# FlightComputer.net
KiCad netlist of a schematic drawn in EAGLE
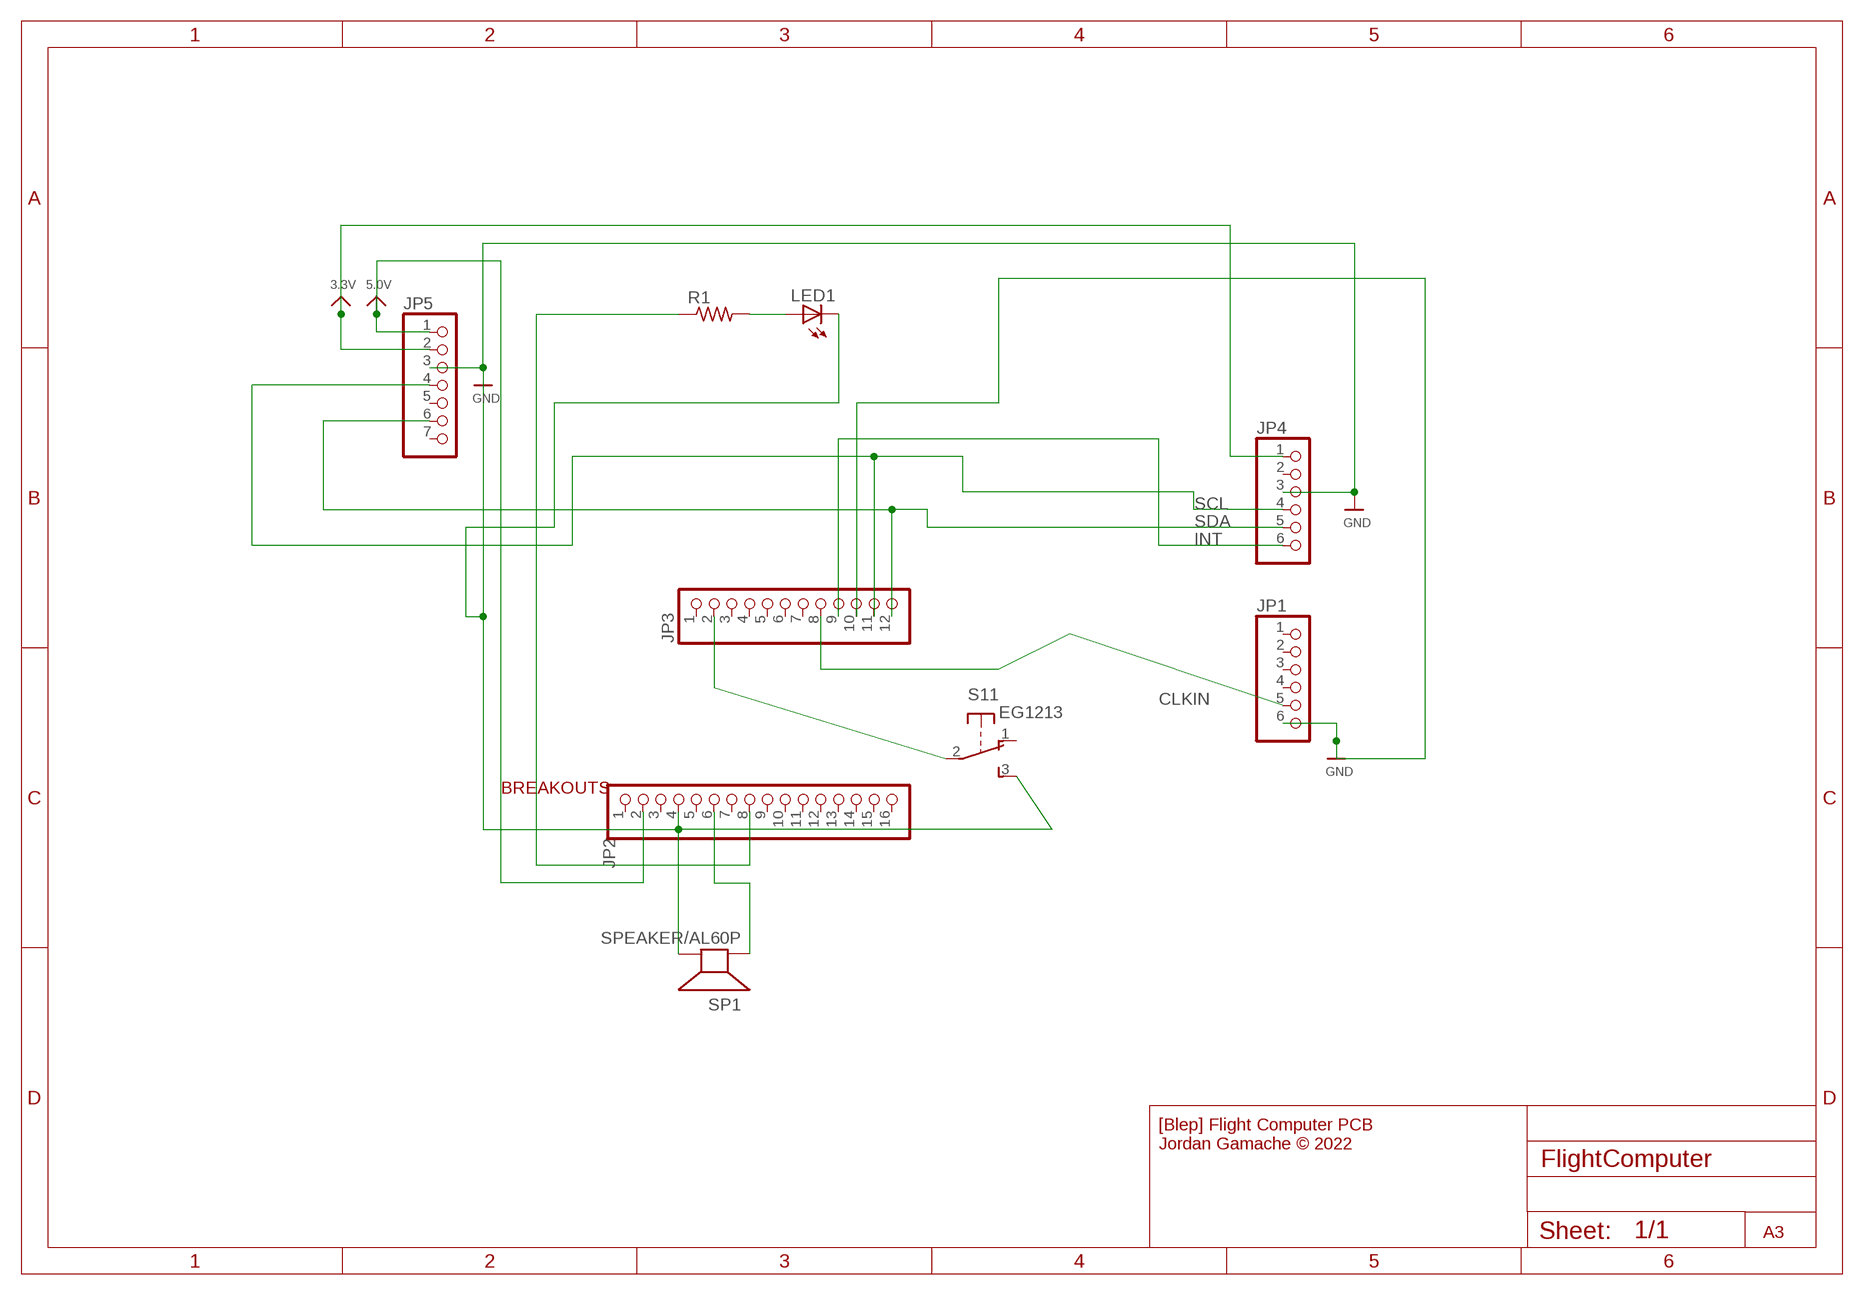
[diagram p0: schematic, sheet 1]

(export (version "E")
  (design (tool "Eeschema 10.0.6"))
  (components
    (comp (ref "JP1")
      (value "HEADER-1X6ROUND")
      (footprint "eagle-import:1X06_ROUND")
      (libsource (lib "eagle-import") (part "HEADER-1X6ROUND"))
    )
    (comp (ref "JP2")
      (value "HEADER-1X16ROUND")
      (footprint "eagle-import:1X16_ROUND")
      (libsource (lib "eagle-import") (part "HEADER-1X16ROUND"))
    )
    (comp (ref "JP3")
      (value "HEADER-1X12")
      (footprint "eagle-import:1X12_ROUND")
      (libsource (lib "eagle-import") (part "HEADER-1X12"))
    )
    (comp (ref "JP4")
      (value "HEADER-1X670MIL")
      (footprint "eagle-import:1X06_ROUND_70")
      (libsource (lib "eagle-import") (part "HEADER-1X670MIL"))
    )
    (comp (ref "JP5")
      (value "HEADER-1X770MIL")
      (footprint "eagle-import:1X07_ROUND_70")
      (libsource (lib "eagle-import") (part "HEADER-1X770MIL"))
    )
    (comp (ref "LED1")
      (value "LED5MM")
      (footprint "eagle-import:LED5MM")
      (libsource (lib "eagle-import") (part "LED5MM"))
    )
    (comp (ref "R1")
      (value "R-US_0207/15")
      (footprint "eagle-import:0207_15")
      (libsource (lib "eagle-import") (part "R-US_0207/15"))
    )
    (comp (ref "S1")
      (value "EG1213")
      (footprint "eagle-import:EG1213")
      (libsource (lib "eagle-import") (part "EG1213"))
    )
    (comp (ref "SP1")
      (value "SPEAKER/AL60P")
      (footprint "eagle-import:AL60P")
      (libsource (lib "eagle-import") (part "SPEAKER/AL60P"))
    )
  )
  (nets
    (net (code "1") (name "/CLKIN") (class "Default")
      (node (ref "JP1") (pin "5") (pinfunction "5_5") (pintype "passive"))
      (node (ref "JP3") (pin "8") (pinfunction "8_8") (pintype "passive"))
    )
    (net (code "2") (name "/INT") (class "Default")
      (node (ref "JP3") (pin "9") (pinfunction "9_9") (pintype "passive"))
      (node (ref "JP4") (pin "6") (pinfunction "6_6") (pintype "passive"))
    )
    (net (code "3") (name "/SCL") (class "Default")
      (node (ref "JP3") (pin "11") (pinfunction "11_11") (pintype "passive"))
      (node (ref "JP4") (pin "4") (pinfunction "4_4") (pintype "passive"))
      (node (ref "JP5") (pin "4") (pinfunction "4_4") (pintype "passive"))
    )
    (net (code "4") (name "/SDA") (class "Default")
      (node (ref "JP3") (pin "12") (pinfunction "12_12") (pintype "passive"))
      (node (ref "JP4") (pin "5") (pinfunction "5_5") (pintype "passive"))
      (node (ref "JP5") (pin "6") (pinfunction "6_6") (pintype "passive"))
    )
    (net (code "5") (name "3.3V") (class "Default")
      (node (ref "JP4") (pin "1") (pinfunction "1_1") (pintype "passive"))
      (node (ref "JP5") (pin "2") (pinfunction "2_2") (pintype "passive"))
    )
    (net (code "6") (name "5.0V") (class "Default")
      (node (ref "JP2") (pin "2") (pinfunction "2_2") (pintype "passive"))
      (node (ref "JP5") (pin "1") (pinfunction "1_1") (pintype "passive"))
    )
    (net (code "7") (name "GND") (class "Default")
      (node (ref "JP1") (pin "6") (pinfunction "6_6") (pintype "passive"))
      (node (ref "JP2") (pin "4") (pinfunction "4_4") (pintype "passive"))
      (node (ref "JP3") (pin "10") (pinfunction "10_10") (pintype "passive"))
      (node (ref "JP4") (pin "3") (pinfunction "3_3") (pintype "passive"))
      (node (ref "JP5") (pin "3") (pinfunction "3_3") (pintype "passive"))
      (node (ref "LED1") (pin "K") (pinfunction "C_K") (pintype "passive"))
      (node (ref "S1") (pin "3") (pinfunction "S_3") (pintype "passive"))
      (node (ref "SP1") (pin "2") (pinfunction "-_2") (pintype "passive"))
    )
    (net (code "8") (name "Net-(JP2-Pad8)") (class "Default")
      (node (ref "JP2") (pin "8") (pinfunction "8_8") (pintype "passive"))
      (node (ref "R1") (pin "1") (pinfunction "1_1") (pintype "passive"))
    )
    (net (code "9") (name "Net-(LED1-PadA)") (class "Default")
      (node (ref "LED1") (pin "A") (pinfunction "A_A") (pintype "passive"))
      (node (ref "R1") (pin "2") (pinfunction "2_2") (pintype "passive"))
    )
    (net (code "10") (name "Net-(S1A-P)") (class "Default")
      (node (ref "JP3") (pin "2") (pinfunction "2_2") (pintype "passive"))
      (node (ref "S1") (pin "2") (pinfunction "P_2") (pintype "passive"))
    )
    (net (code "11") (name "Net-(SP1-+)") (class "Default")
      (node (ref "JP2") (pin "6") (pinfunction "6_6") (pintype "passive"))
      (node (ref "SP1") (pin "1") (pinfunction "+_1") (pintype "passive"))
    )
    (net (code "12") (name "unconnected-(JP1-Pad1)") (class "Default")
      (node (ref "JP1") (pin "1") (pinfunction "1_1") (pintype "passive"))
    )
    (net (code "13") (name "unconnected-(JP1-Pad2)") (class "Default")
      (node (ref "JP1") (pin "2") (pinfunction "2_2") (pintype "passive"))
    )
    (net (code "14") (name "unconnected-(JP1-Pad3)") (class "Default")
      (node (ref "JP1") (pin "3") (pinfunction "3_3") (pintype "passive"))
    )
    (net (code "15") (name "unconnected-(JP1-Pad4)") (class "Default")
      (node (ref "JP1") (pin "4") (pinfunction "4_4") (pintype "passive"))
    )
    (net (code "16") (name "unconnected-(JP2-Pad1)") (class "Default")
      (node (ref "JP2") (pin "1") (pinfunction "1_1") (pintype "passive"))
    )
    (net (code "17") (name "unconnected-(JP2-Pad3)") (class "Default")
      (node (ref "JP2") (pin "3") (pinfunction "3_3") (pintype "passive"))
    )
    (net (code "18") (name "unconnected-(JP2-Pad5)") (class "Default")
      (node (ref "JP2") (pin "5") (pinfunction "5_5") (pintype "passive"))
    )
    (net (code "19") (name "unconnected-(JP2-Pad7)") (class "Default")
      (node (ref "JP2") (pin "7") (pinfunction "7_7") (pintype "passive"))
    )
    (net (code "20") (name "unconnected-(JP2-Pad9)") (class "Default")
      (node (ref "JP2") (pin "9") (pinfunction "9_9") (pintype "passive"))
    )
    (net (code "21") (name "unconnected-(JP2-Pad10)") (class "Default")
      (node (ref "JP2") (pin "10") (pinfunction "10_10") (pintype "passive"))
    )
    (net (code "22") (name "unconnected-(JP2-Pad11)") (class "Default")
      (node (ref "JP2") (pin "11") (pinfunction "11_11") (pintype "passive"))
    )
    (net (code "23") (name "unconnected-(JP2-Pad12)") (class "Default")
      (node (ref "JP2") (pin "12") (pinfunction "12_12") (pintype "passive"))
    )
    (net (code "24") (name "unconnected-(JP2-Pad13)") (class "Default")
      (node (ref "JP2") (pin "13") (pinfunction "13_13") (pintype "passive"))
    )
    (net (code "25") (name "unconnected-(JP2-Pad14)") (class "Default")
      (node (ref "JP2") (pin "14") (pinfunction "14_14") (pintype "passive"))
    )
    (net (code "26") (name "unconnected-(JP2-Pad15)") (class "Default")
      (node (ref "JP2") (pin "15") (pinfunction "15_15") (pintype "passive"))
    )
    (net (code "27") (name "unconnected-(JP2-Pad16)") (class "Default")
      (node (ref "JP2") (pin "16") (pinfunction "16_16") (pintype "passive"))
    )
    (net (code "28") (name "unconnected-(JP3-Pad1)") (class "Default")
      (node (ref "JP3") (pin "1") (pinfunction "1_1") (pintype "passive"))
    )
    (net (code "29") (name "unconnected-(JP3-Pad3)") (class "Default")
      (node (ref "JP3") (pin "3") (pinfunction "3_3") (pintype "passive"))
    )
    (net (code "30") (name "unconnected-(JP3-Pad4)") (class "Default")
      (node (ref "JP3") (pin "4") (pinfunction "4_4") (pintype "passive"))
    )
    (net (code "31") (name "unconnected-(JP3-Pad5)") (class "Default")
      (node (ref "JP3") (pin "5") (pinfunction "5_5") (pintype "passive"))
    )
    (net (code "32") (name "unconnected-(JP3-Pad6)") (class "Default")
      (node (ref "JP3") (pin "6") (pinfunction "6_6") (pintype "passive"))
    )
    (net (code "33") (name "unconnected-(JP3-Pad7)") (class "Default")
      (node (ref "JP3") (pin "7") (pinfunction "7_7") (pintype "passive"))
    )
    (net (code "34") (name "unconnected-(JP4-Pad2)") (class "Default")
      (node (ref "JP4") (pin "2") (pinfunction "2_2") (pintype "passive"))
    )
    (net (code "35") (name "unconnected-(JP5-Pad5)") (class "Default")
      (node (ref "JP5") (pin "5") (pinfunction "5_5") (pintype "passive"))
    )
    (net (code "36") (name "unconnected-(JP5-Pad7)") (class "Default")
      (node (ref "JP5") (pin "7") (pinfunction "7_7") (pintype "passive"))
    )
    (net (code "37") (name "unconnected-(S1A-O-Pad1)") (class "Default")
      (node (ref "S1") (pin "1") (pinfunction "O_1") (pintype "passive"))
    )
  )
)
